# POWER_SUPPLY.net
KiCad netlist of a schematic drawn in Altium Designer
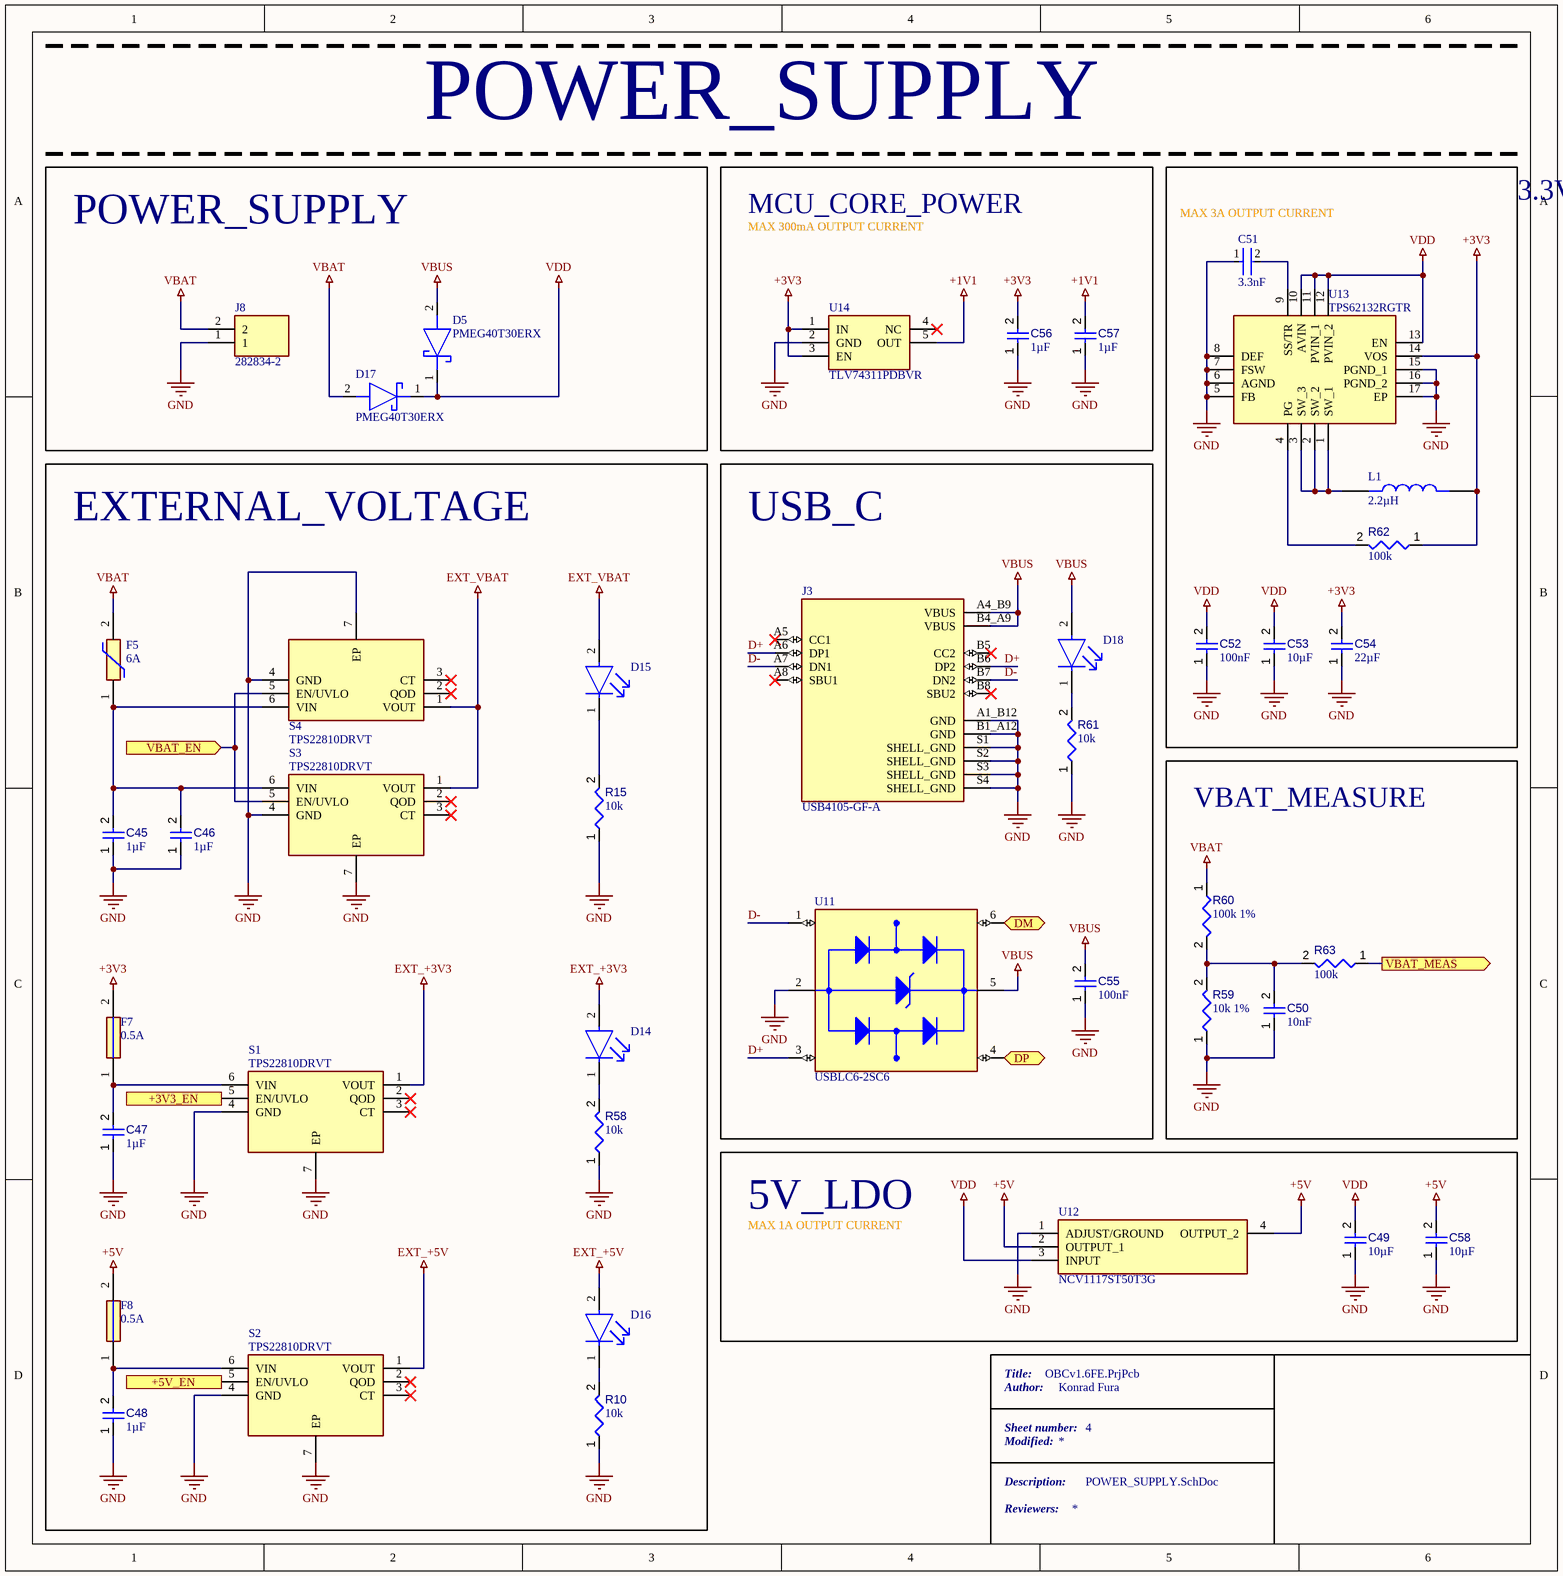
[diagram p0: POWER_SUPPLY.SchDoc]

(export (version "E")
  (design (tool "Eeschema 10.0.6"))
  (components
    (comp (ref "C45")
      (value "1µF")
      (footprint "CAPC0402(1005)60_L")
      (description "Chip Capacitor, 1µF +/-20%, 10V, 0402, Thickness 0.6 mm")
      (fields (field (name "TOLERANCE") "10%") (field (name "Comment") "Capacitor 1µF +/-20% 10V 0402"))
      (libsource (lib "PWr in Space team") (part "CAP-NP-2"))
    )
    (comp (ref "C46")
      (value "1µF")
      (footprint "CAPC0402(1005)60_L")
      (description "Chip Capacitor, 1µF +/-20%, 10V, 0402, Thickness 0.6 mm")
      (fields (field (name "TOLERANCE") "10%") (field (name "Comment") "Capacitor 1µF +/-20% 10V 0402"))
      (libsource (lib "PWr in Space team") (part "CAP-NP-2"))
    )
    (comp (ref "C47")
      (value "1µF")
      (footprint "CAPC0402(1005)60_L")
      (description "Chip Capacitor, 1µF +/-20%, 10V, 0402, Thickness 0.6 mm")
      (fields (field (name "TOLERANCE") "10%") (field (name "Comment") "Capacitor 1µF +/-20% 10V 0402"))
      (libsource (lib "PWr in Space team") (part "CAP-NP-2"))
    )
    (comp (ref "C48")
      (value "1µF")
      (footprint "CAPC0402(1005)60_L")
      (description "Chip Capacitor, 1µF +/-20%, 10V, 0402, Thickness 0.6 mm")
      (fields (field (name "TOLERANCE") "10%") (field (name "Comment") "Capacitor 1µF +/-20% 10V 0402"))
      (libsource (lib "PWr in Space team") (part "CAP-NP-2"))
    )
    (comp (ref "C49")
      (value "10µF")
      (footprint "CAPC0603(1608)100_L")
      (description "Chip Capacitor, 10µF +/-20%, 10V, 0603, Thickness 1 mm")
      (fields (field (name "TOLERANCE") "10%") (field (name "Comment") "Capacitor 10µF +/-20% 10V 0603"))
      (libsource (lib "PWr in Space team") (part "CAP-NP-2"))
    )
    (comp (ref "C50")
      (value "10nF")
      (footprint "CAPC0402(1005)60_L")
      (description "Chip Capacitor, 10nF +/-20%, 50V, 0402, Thickness 0.6 mm")
      (fields (field (name "TOLERANCE") "5%") (field (name "Comment") "Capacitor 10nF +/-20% 50V 0402"))
      (libsource (lib "PWr in Space team") (part "CAP-NP-2"))
    )
    (comp (ref "C51")
      (value "3.3nF")
      (footprint "FP-CL388-IPC_C")
      (description "Cap Ceramic 3.3nF 50V X7R ±10% SMD 0402 +125°C Paper T/R")
      (fields (field (name "TOLERANCE") "10%") (field (name "VOLTAGE") "50V"))
      (libsource (lib "Altium Content Vault") (part "b4654b650e69147ec39a6b967a45e02"))
    )
    (comp (ref "C52")
      (value "100nF")
      (footprint "CAPC0402(1005)60_L")
      (description "Chip Capacitor, 100nF +/-20%, 10V, 0402, Thickness 0.6 mm")
      (fields (field (name "TOLERANCE") "20%") (field (name "Comment") "Capacitor 100nF +/-20% 10V 0402"))
      (libsource (lib "PWr in Space team") (part "CAP-NP-2"))
    )
    (comp (ref "C53")
      (value "10µF")
      (footprint "CAPC0603(1608)100_L")
      (description "Chip Capacitor, 10µF +/-20%, 10V, 0603, Thickness 1 mm")
      (fields (field (name "TOLERANCE") "10%") (field (name "Comment") "Capacitor 10µF +/-20% 10V 0603"))
      (libsource (lib "PWr in Space team") (part "CAP-NP-2"))
    )
    (comp (ref "C54")
      (value "22µF")
      (footprint "CAPC0805(2012)145_L")
      (description "Chip Capacitor, 22µF +/-40%, 16V, 0805, Thickness 1.45 mm")
      (fields (field (name "TOLERANCE") "5%") (field (name "Comment") "Capacitor 22µF +/-40% 16V 0805"))
      (libsource (lib "PWr in Space team") (part "CAP-NP-2"))
    )
    (comp (ref "C55")
      (value "100nF")
      (footprint "CAPC0402(1005)60_L")
      (description "Chip Capacitor, 100nF +/-20%, 10V, 0402, Thickness 0.6 mm")
      (fields (field (name "TOLERANCE") "20%") (field (name "Comment") "Capacitor 100nF +/-20% 10V 0402"))
      (libsource (lib "PWr in Space team") (part "CAP-NP-2"))
    )
    (comp (ref "C56")
      (value "1µF")
      (footprint "CAPC0402(1005)60_L")
      (description "Chip Capacitor, 1µF +/-20%, 10V, 0402, Thickness 0.6 mm")
      (fields (field (name "TOLERANCE") "10%") (field (name "Comment") "Capacitor 1µF +/-20% 10V 0402"))
      (libsource (lib "PWr in Space team") (part "CAP-NP-2"))
    )
    (comp (ref "C57")
      (value "1µF")
      (footprint "CAPC0402(1005)60_L")
      (description "Chip Capacitor, 1µF +/-20%, 10V, 0402, Thickness 0.6 mm")
      (fields (field (name "TOLERANCE") "10%") (field (name "Comment") "Capacitor 1µF +/-20% 10V 0402"))
      (libsource (lib "PWr in Space team") (part "CAP-NP-2"))
    )
    (comp (ref "C58")
      (value "10µF")
      (footprint "CAPC0603(1608)100_L")
      (description "Chip Capacitor, 10µF +/-20%, 10V, 0603, Thickness 1 mm")
      (fields (field (name "TOLERANCE") "10%") (field (name "Comment") "Capacitor 10µF +/-20% 10V 0603"))
      (libsource (lib "PWr in Space team") (part "CAP-NP-2"))
    )
    (comp (ref "D5")
      (value "PMEG40T30ERX")
      (footprint "SamacSys:SODFL3517X110N")
      (description "Schottky Diode")
      (fields
        (field (name "MANUFACTURER_PART_NUMBER") "PMEG60T30ELRX")
        (field (name "MOUSER PART NUMBER") "771-PMEG60T30ELRX")
      )
      (libsource (lib "*") (part "PMEG60T30ELRX"))
    )
    (comp (ref "D14")
      (value "~")
      (footprint "FP-LTST-C191TBKT-MFG")
      (description "LED BLUE CLEAR CHIP SMD")
      (libsource (lib "Altium Content Vault") (part "8706943c75ba83719d021d2fdc84c58"))
    )
    (comp (ref "D15")
      (value "~")
      (footprint "FP-LTST-C191TBKT-MFG")
      (description "LED BLUE CLEAR CHIP SMD")
      (libsource (lib "Altium Content Vault") (part "8706943c75ba83719d021d2fdc84c58"))
    )
    (comp (ref "D16")
      (value "~")
      (footprint "FP-LTST-C191TBKT-MFG")
      (description "LED BLUE CLEAR CHIP SMD")
      (libsource (lib "Altium Content Vault") (part "8706943c75ba83719d021d2fdc84c58"))
    )
    (comp (ref "D17")
      (value "PMEG40T30ERX")
      (footprint "SamacSys:SODFL3517X110N")
      (description "Schottky Diode")
      (fields
        (field (name "MANUFACTURER_PART_NUMBER") "PMEG60T30ELRX")
        (field (name "MOUSER PART NUMBER") "771-PMEG60T30ELRX")
      )
      (libsource (lib "*") (part "PMEG60T30ELRX"))
    )
    (comp (ref "D18")
      (value "~")
      (footprint "FP-LTST-C191TBKT-MFG")
      (description "LED BLUE CLEAR CHIP SMD")
      (libsource (lib "Altium Content Vault") (part "8706943c75ba83719d021d2fdc84c58"))
    )
    (comp (ref "F5")
      (value "6A")
      (footprint "SamacSys:1206L075SLYR")
      (description "Resettable Fuse")
      (fields
        (field (name "MANUFACTURER_PART_NUMBER") "1206L300/12SLYR")
        (field (name "MOUSER PART NUMBER") "576-1206L300/12SLYR")
      )
      (libsource (lib "*") (part "1206L300_12SLYR"))
    )
    (comp (ref "F7")
      (value "0.5A")
      (footprint "SamacSys:FUSC2114X75N")
      (description "Fuse")
      (fields
        (field (name "MANUFACTURER_PART_NUMBER") "0805L020/24YR")
        (field (name "MOUSER PART NUMBER") "576-0805L020/24YR")
      )
      (libsource (lib "*") (part "0805L020_24YR"))
    )
    (comp (ref "F8")
      (value "0.5A")
      (footprint "SamacSys:FUSC2114X75N")
      (description "Fuse")
      (fields
        (field (name "MANUFACTURER_PART_NUMBER") "0805L020/24YR")
        (field (name "MOUSER PART NUMBER") "576-0805L020/24YR")
      )
      (libsource (lib "*") (part "0805L020_24YR"))
    )
    (comp (ref "J3")
      (value "USB4105-GF-A")
      (footprint "GCT_USB4105-GF-A")
      (fields (field (name "MF") "{'manufacturer': u'GCT'}"))
      (libsource (lib "SnapEDA_Library") (part "USB4105-GF-A"))
    )
    (comp (ref "J8")
      (value "282834-2")
      (footprint "SamacSys:282834-2_1")
      (description "Connector")
      (fields (field (name "MOUSER PART NUMBER") "571-282834-2"))
      (libsource (lib "*") (part "282834-2"))
    )
    (comp (ref "L1")
      (value "2.2µH")
      (footprint "IND_XFL4020-102MEC")
      (description "Power inductor, shielded, 20% tol, SMT, RoHS, halogen free")
      (fields (field (name "MF") "{'manufacturer': u'Coilcraft'}") (field (name "MP") "XFL4020-102MEC"))
      (libsource (lib "SnapEDA_Library") (part "XFL4020-102MEC"))
    )
    (comp (ref "R10")
      (value "10k")
      (footprint "RESC0402(1005)_L")
      (description "Chip Resistor, 10 kOhms, +/-1 %, 63 mW, -55 to 125 degC, 0402")
      (fields (field (name "POWER") "63mW") (field (name "TOLERANCE") "1%"))
      (libsource (lib "PWr in Space team") (part "RES-2"))
    )
    (comp (ref "R15")
      (value "10k")
      (footprint "RESC0402(1005)_L")
      (description "Chip Resistor, 10 kOhms, +/-1 %, 63 mW, -55 to 125 degC, 0402")
      (fields (field (name "POWER") "63mW") (field (name "TOLERANCE") "1%"))
      (libsource (lib "PWr in Space team") (part "RES-2"))
    )
    (comp (ref "R58")
      (value "10k")
      (footprint "RESC0402(1005)_L")
      (description "Chip Resistor, 10 kOhms, +/-1 %, 63 mW, -55 to 125 degC, 0402")
      (fields (field (name "POWER") "63mW") (field (name "TOLERANCE") "1%"))
      (libsource (lib "PWr in Space team") (part "RES-2"))
    )
    (comp (ref "R59")
      (value "10k 1%")
      (footprint "RESC0402(1005)_L")
      (description "Chip Resistor, 10 kOhms, +/-1 %, 63 mW, -55 to 125 degC, 0402")
      (fields (field (name "POWER") "63mW") (field (name "TOLERANCE") "1%"))
      (libsource (lib "PWr in Space team") (part "RES-2"))
    )
    (comp (ref "R60")
      (value "100k 1%")
      (footprint "RESC0402(1005)_L")
      (description "Chip Resistor, 100 kOhms, +/-1 %, 63 mW, -55 to 155 degC, 0402")
      (fields (field (name "TOLERANCE") "1%") (field (name "POWER") "63mW"))
      (libsource (lib "PWr in Space team") (part "RES-2"))
    )
    (comp (ref "R61")
      (value "10k")
      (footprint "RESC0402(1005)_L")
      (description "Chip Resistor, 10 kOhms, +/-1 %, 63 mW, -55 to 125 degC, 0402")
      (fields (field (name "POWER") "63mW") (field (name "TOLERANCE") "1%"))
      (libsource (lib "PWr in Space team") (part "RES-2"))
    )
    (comp (ref "R62")
      (value "100k")
      (footprint "RESC0402(1005)_L")
      (description "Chip Resistor, 100 kOhms, +/-1 %, 63 mW, -55 to 155 degC, 0402")
      (fields (field (name "TOLERANCE") "1%") (field (name "POWER") "63mW"))
      (libsource (lib "PWr in Space team") (part "RES-2"))
    )
    (comp (ref "R63")
      (value "100k")
      (footprint "RESC0402(1005)_L")
      (description "Chip Resistor, 100 kOhms, +/-1 %, 63 mW, -55 to 155 degC, 0402")
      (fields (field (name "TOLERANCE") "1%") (field (name "POWER") "63mW"))
      (libsource (lib "PWr in Space team") (part "RES-2"))
    )
    (comp (ref "S1")
      (value "TPS22810DRVT")
      (footprint "SamacSys:SON65P200X200X80-7N")
      (description "Switch")
      (fields (field (name "MOUSER PART NUMBER") "595-TPS22810DRVT"))
      (libsource (lib "*") (part "TPS22810DRVT"))
    )
    (comp (ref "S2")
      (value "TPS22810DRVT")
      (footprint "SamacSys:SON65P200X200X80-7N")
      (description "Switch")
      (fields (field (name "MOUSER PART NUMBER") "595-TPS22810DRVT"))
      (libsource (lib "*") (part "TPS22810DRVT"))
    )
    (comp (ref "S3")
      (value "TPS22810DRVT")
      (footprint "SamacSys:SON65P200X200X80-7N")
      (description "Switch")
      (fields (field (name "MOUSER PART NUMBER") "595-TPS22810DRVT"))
      (libsource (lib "*") (part "TPS22810DRVT"))
    )
    (comp (ref "S4")
      (value "TPS22810DRVT")
      (footprint "SamacSys:SON65P200X200X80-7N")
      (description "Switch")
      (fields (field (name "MOUSER PART NUMBER") "595-TPS22810DRVT"))
      (libsource (lib "") (part "TPS22810DRVT_1"))
    )
    (comp (ref "U11")
      (value "USBLC6-2SC6")
      (footprint "SOT95P280X145-6N")
      (fields (field (name "MF") "{'manufacturer': u'STMicroelectronics'}"))
      (libsource (lib "SnapEDA_Library") (part "USBLC6-2SC6"))
    )
    (comp (ref "U12")
      (value "NCV1117ST50T3G")
      (footprint "SamacSys:SOT230P700X180-4N")
      (description "Integrated Circuit")
      (fields (field (name "MOUSER PART NUMBER") "863-NCV1117ST50T3G"))
      (libsource (lib "*") (part "NCV1117ST50T3G"))
    )
    (comp (ref "U13")
      (value "TPS62132RGTR")
      (footprint "SamacSys:QFN50P300X300X100-17N-D")
      (description "Integrated Circuit")
      (fields (field (name "MOUSER PART NUMBER") "595-TPS62132RGTR"))
      (libsource (lib "*") (part "TPS62132RGTR"))
    )
    (comp (ref "U14")
      (value "TLV74311PDBVR")
      (footprint "SamacSys:SOT95P280X145-5N")
      (description "Integrated Circuit")
      (fields
        (field (name "MANUFACTURER_PART_NUMBER") "TLV70311DBVR")
        (field (name "MOUSER PART NUMBER") "595-TLV70311DBVR")
      )
      (libsource (lib "*") (part "TLV70311DBVR"))
    )
  )
  (nets
    (net (code "1") (name "+1V1") (class "Default")
      (node (ref "C57") (pin "2") (pinfunction "2_2") (pintype "passive"))
      (node (ref "U14") (pin "5") (pinfunction "OUT_5") (pintype "passive"))
    )
    (net (code "2") (name "+3V3") (class "Default")
      (node (ref "C54") (pin "2") (pinfunction "2_2") (pintype "passive"))
      (node (ref "C56") (pin "2") (pinfunction "2_2") (pintype "passive"))
      (node (ref "F7") (pin "2") (pinfunction "2_2") (pintype "passive"))
      (node (ref "L1") (pin "1") (pinfunction "1_1") (pintype "passive"))
      (node (ref "R62") (pin "1") (pinfunction "1_1") (pintype "passive"))
      (node (ref "U13") (pin "14") (pinfunction "VOS_14") (pintype "passive"))
      (node (ref "U14") (pin "1") (pinfunction "IN_1") (pintype "passive"))
      (node (ref "U14") (pin "3") (pinfunction "EN_3") (pintype "passive"))
    )
    (net (code "3") (name "+5V") (class "Default")
      (node (ref "C58") (pin "2") (pinfunction "2_2") (pintype "passive"))
      (node (ref "F8") (pin "2") (pinfunction "2_2") (pintype "passive"))
      (node (ref "U12") (pin "2") (pinfunction "OUTPUT_1_2") (pintype "passive"))
      (node (ref "U12") (pin "4") (pinfunction "OUTPUT_2_4") (pintype "passive"))
    )
    (net (code "4") (name "/+3V3_EN") (class "Default")
      (node (ref "S1") (pin "5") (pinfunction "EN/UVLO_5") (pintype "passive"))
    )
    (net (code "5") (name "/+5V_EN") (class "Default")
      (node (ref "S2") (pin "5") (pinfunction "EN/UVLO_5") (pintype "passive"))
    )
    (net (code "6") (name "/D+") (class "Default")
      (node (ref "J3") (pin "A6") (pinfunction "DP1_A6") (pintype "bidirectional"))
      (node (ref "J3") (pin "B6") (pinfunction "DP2_B6") (pintype "bidirectional"))
      (node (ref "U11") (pin "3") (pinfunction "I/O2_IN_3") (pintype "bidirectional"))
    )
    (net (code "7") (name "/D-") (class "Default")
      (node (ref "J3") (pin "A7") (pinfunction "DN1_A7") (pintype "bidirectional"))
      (node (ref "J3") (pin "B7") (pinfunction "DN2_B7") (pintype "bidirectional"))
      (node (ref "U11") (pin "1") (pinfunction "I/O1_IN_1") (pintype "bidirectional"))
    )
    (net (code "8") (name "/DM") (class "Default")
      (node (ref "U11") (pin "6") (pinfunction "I/O1_OUT_6") (pintype "bidirectional"))
    )
    (net (code "9") (name "/DP") (class "Default")
      (node (ref "U11") (pin "4") (pinfunction "I/O2_OUT_4") (pintype "bidirectional"))
    )
    (net (code "10") (name "/VBAT_EN") (class "Default")
      (node (ref "S3") (pin "5") (pinfunction "EN/UVLO_5") (pintype "passive"))
      (node (ref "S4") (pin "5") (pinfunction "EN/UVLO_5") (pintype "passive"))
    )
    (net (code "11") (name "/VBAT_MEAS") (class "Default")
      (node (ref "R63") (pin "1") (pinfunction "1_1") (pintype "passive"))
    )
    (net (code "12") (name "EXT_+3V3") (class "Default")
      (node (ref "D14") (pin "2") (pinfunction "A_2") (pintype "passive"))
      (node (ref "S1") (pin "1") (pinfunction "VOUT_1") (pintype "passive"))
    )
    (net (code "13") (name "EXT_+5V") (class "Default")
      (node (ref "D16") (pin "2") (pinfunction "A_2") (pintype "passive"))
      (node (ref "S2") (pin "1") (pinfunction "VOUT_1") (pintype "passive"))
    )
    (net (code "14") (name "EXT_VBAT") (class "Default")
      (node (ref "D15") (pin "2") (pinfunction "A_2") (pintype "passive"))
      (node (ref "S3") (pin "1") (pinfunction "VOUT_1") (pintype "passive"))
      (node (ref "S4") (pin "1") (pinfunction "VOUT_1") (pintype "passive"))
    )
    (net (code "15") (name "GND") (class "Default")
      (node (ref "C45") (pin "1") (pinfunction "1_1") (pintype "passive"))
      (node (ref "C46") (pin "1") (pinfunction "1_1") (pintype "passive"))
      (node (ref "C47") (pin "1") (pinfunction "1_1") (pintype "passive"))
      (node (ref "C48") (pin "1") (pinfunction "1_1") (pintype "passive"))
      (node (ref "C49") (pin "1") (pinfunction "1_1") (pintype "passive"))
      (node (ref "C50") (pin "1") (pinfunction "1_1") (pintype "passive"))
      (node (ref "C51") (pin "1") (pinfunction "1_1") (pintype "passive"))
      (node (ref "C52") (pin "1") (pinfunction "1_1") (pintype "passive"))
      (node (ref "C53") (pin "1") (pinfunction "1_1") (pintype "passive"))
      (node (ref "C54") (pin "1") (pinfunction "1_1") (pintype "passive"))
      (node (ref "C55") (pin "1") (pinfunction "1_1") (pintype "passive"))
      (node (ref "C56") (pin "1") (pinfunction "1_1") (pintype "passive"))
      (node (ref "C57") (pin "1") (pinfunction "1_1") (pintype "passive"))
      (node (ref "C58") (pin "1") (pinfunction "1_1") (pintype "passive"))
      (node (ref "J3") (pin "A1_B12") (pinfunction "GND_A1_B12") (pintype "power_in"))
      (node (ref "J3") (pin "B1_A12") (pinfunction "GND_B1_A12") (pintype "power_in"))
      (node (ref "J3") (pin "S1") (pinfunction "SHELL_GND_S1") (pintype "power_in"))
      (node (ref "J3") (pin "S2") (pinfunction "SHELL_GND_S2") (pintype "power_in"))
      (node (ref "J3") (pin "S3") (pinfunction "SHELL_GND_S3") (pintype "power_in"))
      (node (ref "J3") (pin "S4") (pinfunction "SHELL_GND_S4") (pintype "power_in"))
      (node (ref "J8") (pin "1") (pinfunction "1_1") (pintype "passive"))
      (node (ref "R10") (pin "1") (pinfunction "1_1") (pintype "passive"))
      (node (ref "R15") (pin "1") (pinfunction "1_1") (pintype "passive"))
      (node (ref "R58") (pin "1") (pinfunction "1_1") (pintype "passive"))
      (node (ref "R59") (pin "1") (pinfunction "1_1") (pintype "passive"))
      (node (ref "R61") (pin "1") (pinfunction "1_1") (pintype "passive"))
      (node (ref "S1") (pin "4") (pinfunction "GND_4") (pintype "passive"))
      (node (ref "S1") (pin "7") (pinfunction "EP_7") (pintype "passive"))
      (node (ref "S2") (pin "4") (pinfunction "GND_4") (pintype "passive"))
      (node (ref "S2") (pin "7") (pinfunction "EP_7") (pintype "passive"))
      (node (ref "S3") (pin "4") (pinfunction "GND_4") (pintype "passive"))
      (node (ref "S3") (pin "7") (pinfunction "EP_7") (pintype "passive"))
      (node (ref "S4") (pin "4") (pinfunction "GND_4") (pintype "passive"))
      (node (ref "S4") (pin "7") (pinfunction "EP_7") (pintype "passive"))
      (node (ref "U11") (pin "2") (pinfunction "GND_2") (pintype "power_in"))
      (node (ref "U12") (pin "1") (pinfunction "ADJUST/GROUND_1") (pintype "passive"))
      (node (ref "U13") (pin "15") (pinfunction "PGND_1_15") (pintype "passive"))
      (node (ref "U13") (pin "16") (pinfunction "PGND_2_16") (pintype "passive"))
      (node (ref "U13") (pin "17") (pinfunction "EP_17") (pintype "passive"))
      (node (ref "U13") (pin "5") (pinfunction "FB_5") (pintype "passive"))
      (node (ref "U13") (pin "6") (pinfunction "AGND_6") (pintype "passive"))
      (node (ref "U13") (pin "7") (pinfunction "FSW_7") (pintype "passive"))
      (node (ref "U13") (pin "8") (pinfunction "DEF_8") (pintype "passive"))
      (node (ref "U14") (pin "2") (pinfunction "GND_2") (pintype "passive"))
    )
    (net (code "16") (name "Net-(C50-Pad2)") (class "Default")
      (node (ref "C50") (pin "2") (pinfunction "2_2") (pintype "passive"))
      (node (ref "R59") (pin "2") (pinfunction "2_2") (pintype "passive"))
      (node (ref "R60") (pin "2") (pinfunction "2_2") (pintype "passive"))
      (node (ref "R63") (pin "2") (pinfunction "2_2") (pintype "passive"))
    )
    (net (code "17") (name "Net-(D14-C)") (class "Default")
      (node (ref "D14") (pin "1") (pinfunction "C_1") (pintype "passive"))
      (node (ref "R58") (pin "2") (pinfunction "2_2") (pintype "passive"))
    )
    (net (code "18") (name "Net-(D15-C)") (class "Default")
      (node (ref "D15") (pin "1") (pinfunction "C_1") (pintype "passive"))
      (node (ref "R15") (pin "2") (pinfunction "2_2") (pintype "passive"))
    )
    (net (code "19") (name "Net-(D16-C)") (class "Default")
      (node (ref "D16") (pin "1") (pinfunction "C_1") (pintype "passive"))
      (node (ref "R10") (pin "2") (pinfunction "2_2") (pintype "passive"))
    )
    (net (code "20") (name "Net-(D18-C)") (class "Default")
      (node (ref "D18") (pin "1") (pinfunction "C_1") (pintype "passive"))
      (node (ref "R61") (pin "2") (pinfunction "2_2") (pintype "passive"))
    )
    (net (code "21") (name "Net-(S1-VIN)") (class "Default")
      (node (ref "C47") (pin "2") (pinfunction "2_2") (pintype "passive"))
      (node (ref "F7") (pin "1") (pinfunction "1_1") (pintype "passive"))
      (node (ref "S1") (pin "6") (pinfunction "VIN_6") (pintype "passive"))
    )
    (net (code "22") (name "Net-(S2-VIN)") (class "Default")
      (node (ref "C48") (pin "2") (pinfunction "2_2") (pintype "passive"))
      (node (ref "F8") (pin "1") (pinfunction "1_1") (pintype "passive"))
      (node (ref "S2") (pin "6") (pinfunction "VIN_6") (pintype "passive"))
    )
    (net (code "23") (name "Net-(S3-VIN)") (class "Default")
      (node (ref "C45") (pin "2") (pinfunction "2_2") (pintype "passive"))
      (node (ref "C46") (pin "2") (pinfunction "2_2") (pintype "passive"))
      (node (ref "F5") (pin "1") (pinfunction "1_1") (pintype "passive"))
      (node (ref "S3") (pin "6") (pinfunction "VIN_6") (pintype "passive"))
      (node (ref "S4") (pin "6") (pinfunction "VIN_6") (pintype "passive"))
    )
    (net (code "24") (name "Net-(U13-PG)") (class "Default")
      (node (ref "R62") (pin "2") (pinfunction "2_2") (pintype "passive"))
      (node (ref "U13") (pin "4") (pinfunction "PG_4") (pintype "passive"))
    )
    (net (code "25") (name "Net-(U13-SS{slash}TR)") (class "Default")
      (node (ref "C51") (pin "2") (pinfunction "2_2") (pintype "passive"))
      (node (ref "U13") (pin "9") (pinfunction "SS/TR_9") (pintype "passive"))
    )
    (net (code "26") (name "Net-(U13-SW_1)") (class "Default")
      (node (ref "L1") (pin "2") (pinfunction "2_2") (pintype "passive"))
      (node (ref "U13") (pin "1") (pinfunction "SW_1_1") (pintype "passive"))
      (node (ref "U13") (pin "2") (pinfunction "SW_2_2") (pintype "passive"))
      (node (ref "U13") (pin "3") (pinfunction "SW_3_3") (pintype "passive"))
    )
    (net (code "27") (name "VBAT") (class "Default")
      (node (ref "D17") (pin "2") (pinfunction "A_2") (pintype "passive"))
      (node (ref "F5") (pin "2") (pinfunction "2_2") (pintype "passive"))
      (node (ref "J8") (pin "2") (pinfunction "2_2") (pintype "passive"))
      (node (ref "R60") (pin "1") (pinfunction "1_1") (pintype "passive"))
    )
    (net (code "28") (name "VBUS") (class "Default")
      (node (ref "C55") (pin "2") (pinfunction "2_2") (pintype "passive"))
      (node (ref "D18") (pin "2") (pinfunction "A_2") (pintype "passive"))
      (node (ref "D5") (pin "2") (pinfunction "A_2") (pintype "passive"))
      (node (ref "J3") (pin "A4_B9") (pinfunction "VBUS_A4_B9") (pintype "power_in"))
      (node (ref "J3") (pin "B4_A9") (pinfunction "VBUS_B4_A9") (pintype "power_in"))
      (node (ref "U11") (pin "5") (pinfunction "VBUS_5") (pintype "power_in"))
    )
    (net (code "29") (name "VDD") (class "Default")
      (node (ref "C49") (pin "2") (pinfunction "2_2") (pintype "passive"))
      (node (ref "C52") (pin "2") (pinfunction "2_2") (pintype "passive"))
      (node (ref "C53") (pin "2") (pinfunction "2_2") (pintype "passive"))
      (node (ref "D17") (pin "1") (pinfunction "K_1") (pintype "passive"))
      (node (ref "D5") (pin "1") (pinfunction "K_1") (pintype "passive"))
      (node (ref "U12") (pin "3") (pinfunction "INPUT_3") (pintype "passive"))
      (node (ref "U13") (pin "10") (pinfunction "AVIN_10") (pintype "passive"))
      (node (ref "U13") (pin "11") (pinfunction "PVIN_1_11") (pintype "passive"))
      (node (ref "U13") (pin "12") (pinfunction "PVIN_2_12") (pintype "passive"))
      (node (ref "U13") (pin "13") (pinfunction "EN_13") (pintype "passive"))
    )
    (net (code "30") (name "unconnected-(J3-CC1-PadA5)") (class "Default")
      (node (ref "J3") (pin "A5") (pinfunction "CC1_A5") (pintype "bidirectional+no_connect"))
    )
    (net (code "31") (name "unconnected-(J3-CC2-PadB5)") (class "Default")
      (node (ref "J3") (pin "B5") (pinfunction "CC2_B5") (pintype "bidirectional+no_connect"))
    )
    (net (code "32") (name "unconnected-(J3-SBU1-PadA8)") (class "Default")
      (node (ref "J3") (pin "A8") (pinfunction "SBU1_A8") (pintype "bidirectional+no_connect"))
    )
    (net (code "33") (name "unconnected-(J3-SBU2-PadB8)") (class "Default")
      (node (ref "J3") (pin "B8") (pinfunction "SBU2_B8") (pintype "bidirectional+no_connect"))
    )
    (net (code "34") (name "unconnected-(S1-CT-Pad3)") (class "Default")
      (node (ref "S1") (pin "3") (pinfunction "CT_3") (pintype "passive+no_connect"))
    )
    (net (code "35") (name "unconnected-(S1-QOD-Pad2)") (class "Default")
      (node (ref "S1") (pin "2") (pinfunction "QOD_2") (pintype "passive+no_connect"))
    )
    (net (code "36") (name "unconnected-(S2-CT-Pad3)") (class "Default")
      (node (ref "S2") (pin "3") (pinfunction "CT_3") (pintype "passive+no_connect"))
    )
    (net (code "37") (name "unconnected-(S2-QOD-Pad2)") (class "Default")
      (node (ref "S2") (pin "2") (pinfunction "QOD_2") (pintype "passive+no_connect"))
    )
    (net (code "38") (name "unconnected-(S3-CT-Pad3)") (class "Default")
      (node (ref "S3") (pin "3") (pinfunction "CT_3") (pintype "passive+no_connect"))
    )
    (net (code "39") (name "unconnected-(S3-QOD-Pad2)") (class "Default")
      (node (ref "S3") (pin "2") (pinfunction "QOD_2") (pintype "passive+no_connect"))
    )
    (net (code "40") (name "unconnected-(S4-CT-Pad3)") (class "Default")
      (node (ref "S4") (pin "3") (pinfunction "CT_3") (pintype "passive+no_connect"))
    )
    (net (code "41") (name "unconnected-(S4-QOD-Pad2)") (class "Default")
      (node (ref "S4") (pin "2") (pinfunction "QOD_2") (pintype "passive+no_connect"))
    )
    (net (code "42") (name "unconnected-(U14-NC-Pad4)") (class "Default")
      (node (ref "U14") (pin "4") (pinfunction "NC_4") (pintype "passive+no_connect"))
    )
  )
)
